# blinky_ver2.net
KiCad netlist of a schematic drawn in EAGLE
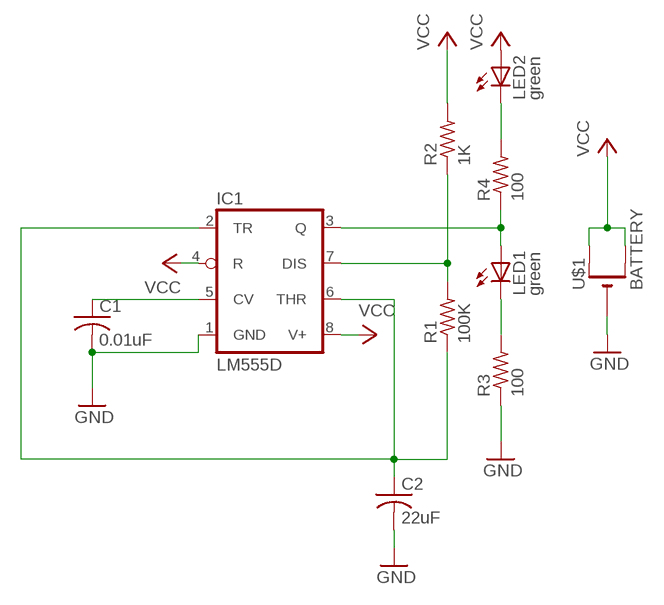
[diagram p0: schematic, sheet 1]

(export (version "E")
  (design (tool "Eeschema 10.0.6"))
  (components
    (comp (ref "C1")
      (value "0.01uF")
      (footprint "eagle-import:C0805")
      (libsource (lib "eagle-import") (part "C-USC0805"))
    )
    (comp (ref "C2")
      (value "22uF")
      (footprint "eagle-import:C0805")
      (libsource (lib "eagle-import") (part "C-USC0805"))
    )
    (comp (ref "IC1")
      (value "LM555D")
      (footprint "eagle-import:SO08")
      (libsource (lib "eagle-import") (part "555DLM"))
    )
    (comp (ref "LED1")
      (value "green")
      (footprint "eagle-import:CHIPLED_0805")
      (libsource (lib "eagle-import") (part "LEDCHIPLED_0805"))
    )
    (comp (ref "LED2")
      (value "green")
      (footprint "eagle-import:CHIPLED_0805")
      (libsource (lib "eagle-import") (part "LEDCHIPLED_0805"))
    )
    (comp (ref "R1")
      (value "100K")
      (footprint "eagle-import:R0805")
      (libsource (lib "eagle-import") (part "R-US_R0805"))
    )
    (comp (ref "R2")
      (value "1K")
      (footprint "eagle-import:R0805")
      (libsource (lib "eagle-import") (part "R-US_R0805"))
    )
    (comp (ref "R3")
      (value "100")
      (footprint "eagle-import:R0805")
      (libsource (lib "eagle-import") (part "R-US_R0805"))
    )
    (comp (ref "R4")
      (value "100")
      (footprint "eagle-import:R0805")
      (libsource (lib "eagle-import") (part "R-US_R0805"))
    )
    (comp (ref "U$1")
      (value "BATTERY")
      (footprint "eagle-import:CR1220-SMD")
      (libsource (lib "eagle-import") (part "CR1220SMT"))
    )
  )
  (nets
    (net (code "1") (name "GND") (class "Default")
      (node (ref "C1") (pin "2") (pinfunction "2_2") (pintype "passive"))
      (node (ref "C2") (pin "2") (pinfunction "2_2") (pintype "passive"))
      (node (ref "IC1") (pin "1") (pinfunction "GND_1") (pintype "power_in"))
      (node (ref "R3") (pin "1") (pinfunction "1_1") (pintype "passive"))
      (node (ref "U$1") (pin "-") (pinfunction "-_-") (pintype "passive"))
    )
    (net (code "2") (name "Net-(IC1-CV)") (class "Default")
      (node (ref "C1") (pin "1") (pinfunction "1_1") (pintype "passive"))
      (node (ref "IC1") (pin "5") (pinfunction "CV_5") (pintype "input"))
    )
    (net (code "3") (name "Net-(IC1-DIS)") (class "Default")
      (node (ref "IC1") (pin "7") (pinfunction "DIS_7") (pintype "input"))
      (node (ref "R1") (pin "2") (pinfunction "2_2") (pintype "passive"))
      (node (ref "R2") (pin "1") (pinfunction "1_1") (pintype "passive"))
    )
    (net (code "4") (name "Net-(IC1-Q)") (class "Default")
      (node (ref "IC1") (pin "3") (pinfunction "Q_3") (pintype "output"))
      (node (ref "LED1") (pin "A") (pinfunction "A_A") (pintype "passive"))
      (node (ref "R4") (pin "1") (pinfunction "1_1") (pintype "passive"))
    )
    (net (code "5") (name "Net-(IC1-THR)") (class "Default")
      (node (ref "C2") (pin "1") (pinfunction "1_1") (pintype "passive"))
      (node (ref "IC1") (pin "2") (pinfunction "TR_2") (pintype "input"))
      (node (ref "IC1") (pin "6") (pinfunction "THR_6") (pintype "input"))
      (node (ref "R1") (pin "1") (pinfunction "1_1") (pintype "passive"))
    )
    (net (code "6") (name "Net-(LED1-PadC)") (class "Default")
      (node (ref "LED1") (pin "C") (pinfunction "C_C") (pintype "passive"))
      (node (ref "R3") (pin "2") (pinfunction "2_2") (pintype "passive"))
    )
    (net (code "7") (name "Net-(LED2-PadC)") (class "Default")
      (node (ref "LED2") (pin "C") (pinfunction "C_C") (pintype "passive"))
      (node (ref "R4") (pin "2") (pinfunction "2_2") (pintype "passive"))
    )
    (net (code "8") (name "VCC") (class "Default")
      (node (ref "IC1") (pin "4") (pinfunction "R_4") (pintype "input"))
      (node (ref "IC1") (pin "8") (pinfunction "V+_8") (pintype "power_in"))
      (node (ref "LED2") (pin "A") (pinfunction "A_A") (pintype "passive"))
      (node (ref "R2") (pin "2") (pinfunction "2_2") (pintype "passive"))
      (node (ref "U$1") (pin "+$1") (pinfunction "+_+$1") (pintype "passive"))
      (node (ref "U$1") (pin "+$2") (pinfunction "+1_+$2") (pintype "passive"))
    )
  )
)
